# Condor2a_Power_REV_C.net
KiCad netlist of a schematic drawn in Altium Designer
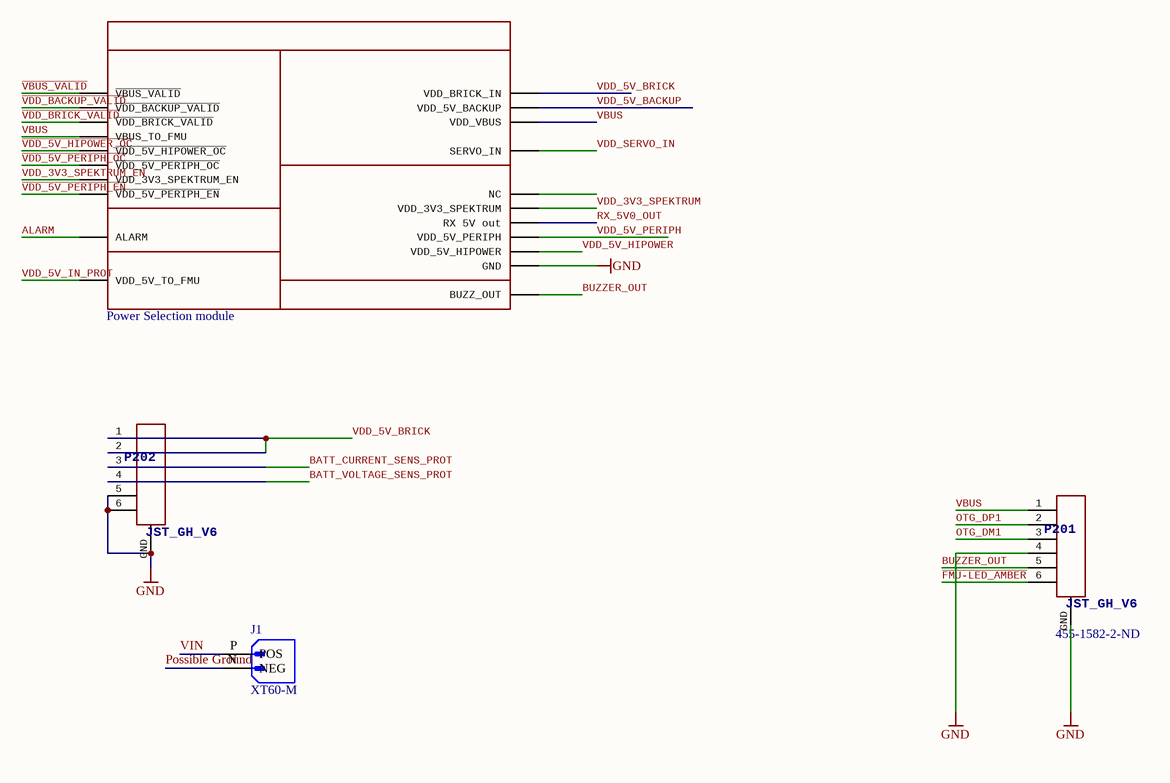
[diagram p0: Condor2a_Power_REV_C.SchDoc]

(export (version "E")
  (design (tool "Eeschema 10.0.6"))
  (components
    (comp (ref "J1")
      (value "XT60-M")
      (footprint "AMASS_XT60-M")
      (description "Plug; DC supply; XT60; male; PIN: 2; for cable; soldered; 30A; 500V")
      (fields (field (name "MF") "AMASS"))
      (libsource (lib "CB_REV_C") (part "XT60-M"))
    )
    (comp (ref "P201")
      (value "JST_GH_V6")
      (footprint "JST_GH_V6")
      (description "BM06B-GHS-TBT")
      (fields (field (name "SUPPLIER PART NUMBER 1") "455-1582-2-ND"))
      (libsource (lib "CB_REV_C") (part "JST_GH_V6"))
    )
    (comp (ref "P202")
      (value "JST_GH_V6")
      (footprint "JST_GH_V6")
      (description "BM06B-GHS-TBT")
      (libsource (lib "CB_REV_C") (part "JST_GH_V6"))
    )
    (comp (ref "PSM200")
      (value "Power Selection module")
      (footprint "PSM")
      (description "PCA, PSM, Assembly")
      (libsource (lib "CB_REV_C") (part "PSMPSM"))
    )
  )
  (nets
    (net (code "1") (name "/ALARM") (class "Default")
      (node (ref "PSM200") (pin "ALARM") (pinfunction "ALARM_ALARM") (pintype "passive"))
    )
    (net (code "2") (name "/BATT_CURRENT_SENS_PROT") (class "Default")
      (node (ref "P202") (pin "3") (pinfunction "3_3") (pintype "passive"))
    )
    (net (code "3") (name "/BATT_VOLTAGE_SENS_PROT") (class "Default")
      (node (ref "P202") (pin "4") (pinfunction "4_4") (pintype "passive"))
    )
    (net (code "4") (name "/BUZZER_OUT") (class "Default")
      (node (ref "P201") (pin "5") (pinfunction "5_5") (pintype "passive"))
      (node (ref "PSM200") (pin "BUZZER_OUT") (pinfunction "BUZZ_OUT_BUZZER_OUT") (pintype "passive"))
    )
    (net (code "5") (name "/OTG_DM1") (class "Default")
      (node (ref "P201") (pin "3") (pinfunction "3_3") (pintype "passive"))
    )
    (net (code "6") (name "/OTG_DP1") (class "Default")
      (node (ref "P201") (pin "2") (pinfunction "2_2") (pintype "passive"))
    )
    (net (code "7") (name "/Possible Ground") (class "Default")
      (node (ref "J1") (pin "N") (pinfunction "NEG_N") (pintype "passive"))
    )
    (net (code "8") (name "/RX_5V0_OUT") (class "Default")
      (node (ref "PSM200") (pin "RX") (pinfunction "RX_5V_out_RX") (pintype "passive"))
    )
    (net (code "9") (name "/VBUS") (class "Default")
      (node (ref "P201") (pin "1") (pinfunction "1_1") (pintype "passive"))
      (node (ref "PSM200") (pin "VBUS") (pinfunction "VBUS_TO_FMU_VBUS") (pintype "passive"))
      (node (ref "PSM200") (pin "VDD_VBUS") (pinfunction "VDD_VBUS_VDD_VBUS") (pintype "passive"))
    )
    (net (code "10") (name "/VDD_3V3_SPEKTRUM") (class "Default")
      (node (ref "PSM200") (pin "SPEK") (pinfunction "VDD_3V3_SPEKTRUM_SPEK") (pintype "passive"))
    )
    (net (code "11") (name "/VDD_3V3_SPEKTRUM_EN") (class "Default")
      (node (ref "PSM200") (pin "VDD_3V3_SPEKTRUM_EN") (pinfunction "VDD_3V3_SPEKTRUM_EN_VDD_3V3_SPEKTRUM_EN") (pintype "passive"))
    )
    (net (code "12") (name "/VDD_5V_BACKUP") (class "Default")
      (node (ref "PSM200") (pin "VDD_5V_BACKUP") (pinfunction "VDD_5V_BACKUP_VDD_5V_BACKUP") (pintype "passive"))
    )
    (net (code "13") (name "/VDD_5V_BRICK") (class "Default")
      (node (ref "P202") (pin "1") (pinfunction "1_1") (pintype "passive"))
      (node (ref "P202") (pin "2") (pinfunction "2_2") (pintype "passive"))
      (node (ref "PSM200") (pin "VDD_BRICK_IN") (pinfunction "VDD_BRICK_IN_VDD_BRICK_IN") (pintype "passive"))
    )
    (net (code "14") (name "/VDD_5V_HIPOWER") (class "Default")
      (node (ref "PSM200") (pin "5V_HIPOWER") (pinfunction "VDD_5V_HIPOWER_5V_HIPOWER") (pintype "passive"))
    )
    (net (code "15") (name "/VDD_5V_IN_PROT") (class "Default")
      (node (ref "PSM200") (pin "VDD_5V_IN_PROT") (pinfunction "VDD_5V_TO_FMU_VDD_5V_IN_PROT") (pintype "passive"))
    )
    (net (code "16") (name "/VDD_5V_PERIPH") (class "Default")
      (node (ref "PSM200") (pin "5V_PERIPH") (pinfunction "VDD_5V_PERIPH_5V_PERIPH") (pintype "passive"))
    )
    (net (code "17") (name "/VDD_SERVO_IN") (class "Default")
      (node (ref "PSM200") (pin "SERVO_IN") (pinfunction "SERVO_IN_SERVO_IN") (pintype "passive"))
    )
    (net (code "18") (name "/VIN") (class "Default")
      (node (ref "J1") (pin "P") (pinfunction "POS_P") (pintype "passive"))
    )
    (net (code "19") (name "/~{FMU-LED_AMBER}") (class "Default")
      (node (ref "P201") (pin "6") (pinfunction "6_6") (pintype "passive"))
    )
    (net (code "20") (name "/~{VBUS_VALID}") (class "Default")
      (node (ref "PSM200") (pin "!VBUS_VALID") (pinfunction "~{VBUS_VALID}_!VBUS_VALID") (pintype "passive"))
    )
    (net (code "21") (name "/~{VDD_5V_HIPOWER_OC}") (class "Default")
      (node (ref "PSM200") (pin "!VDD_5V_HIPOWER_OC") (pinfunction "~{VDD_5V_HIPOWER_OC}_!VDD_5V_HIPOWER_OC") (pintype "passive"))
    )
    (net (code "22") (name "/~{VDD_5V_PERIPH_EN}") (class "Default")
      (node (ref "PSM200") (pin "!VDD_5V_PERIPH_EN") (pinfunction "~{VDD_5V_PERIPH_EN}_!VDD_5V_PERIPH_EN") (pintype "passive"))
    )
    (net (code "23") (name "/~{VDD_5V_PERIPH_OC}") (class "Default")
      (node (ref "PSM200") (pin "!VDD_5V_PERIPH_OC") (pinfunction "~{VDD_5V_PERIPH_OC}_!VDD_5V_PERIPH_OC") (pintype "passive"))
    )
    (net (code "24") (name "/~{VDD_BACKUP_VALID}") (class "Default")
      (node (ref "PSM200") (pin "!VDD_BACKUP_VALID") (pinfunction "~{VDD_BACKUP_VALID}_!VDD_BACKUP_VALID") (pintype "passive"))
    )
    (net (code "25") (name "/~{VDD_BRICK_VALID}") (class "Default")
      (node (ref "PSM200") (pin "!VDD_BRICK_VALID") (pinfunction "~{VDD_BRICK_VALID}_!VDD_BRICK_VALID") (pintype "passive"))
    )
    (net (code "26") (name "GND") (class "Default")
      (node (ref "P201") (pin "4") (pinfunction "4_4") (pintype "passive"))
      (node (ref "P201") (pin "GND") (pinfunction "GND_GND") (pintype "passive"))
      (node (ref "P202") (pin "5") (pinfunction "5_5") (pintype "passive"))
      (node (ref "P202") (pin "6") (pinfunction "6_6") (pintype "passive"))
      (node (ref "P202") (pin "GND") (pinfunction "GND_GND") (pintype "passive"))
      (node (ref "PSM200") (pin "GND") (pinfunction "GND_GND") (pintype "passive"))
    )
    (net (code "27") (name "unconnected-(PSM200-PadNC)") (class "Default")
      (node (ref "PSM200") (pin "NC") (pinfunction "NC_NC") (pintype "passive"))
    )
  )
)
